# usbB_isp_no_lm2940.net
KiCad netlist of a schematic drawn in EAGLE
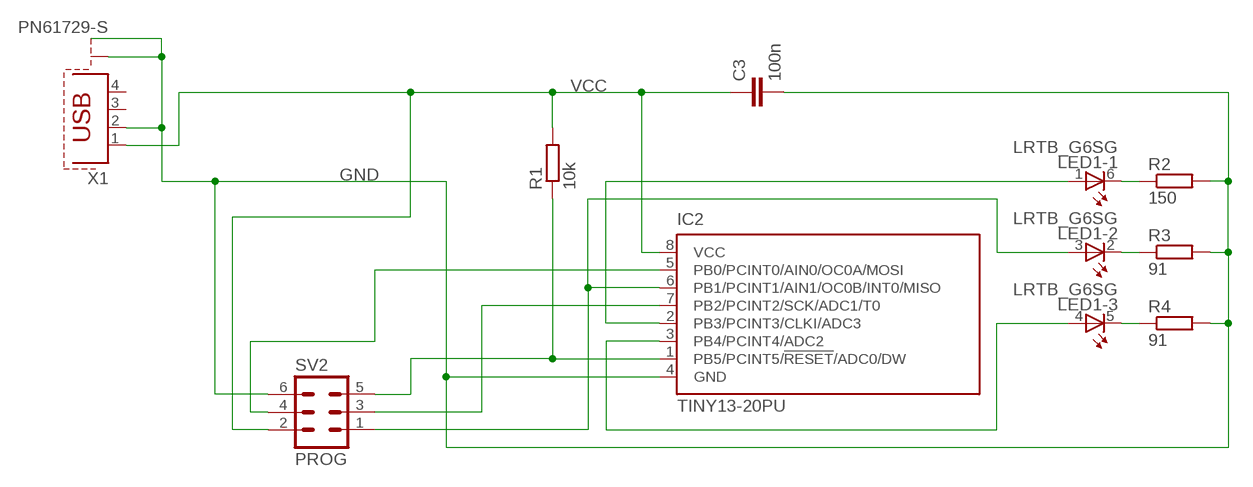
[diagram p0: schematic, sheet 1]

(export (version "E")
  (design (tool "Eeschema 10.0.6"))
  (components
    (comp (ref "C3")
      (value "100n")
      (footprint "eagle-import:C025-025X050")
      (libsource (lib "eagle-import") (part "C-EU025-025X050"))
    )
    (comp (ref "IC2")
      (value "TINY13-20PU")
      (footprint "eagle-import:DIL08")
      (fields (field (name "MPN") "ATTINY13-20PU"))
      (libsource (lib "eagle-import") (part "TINY13PU-20"))
    )
    (comp (ref "LED1")
      (value "LRTB_G6SG")
      (footprint "eagle-import:LRTB_G6SG")
      (libsource (lib "eagle-import") (part "LRTB_G6SG"))
    )
    (comp (ref "R1")
      (value "10k")
      (footprint "eagle-import:0207_10")
      (libsource (lib "eagle-import") (part "R-EU_0207/10"))
    )
    (comp (ref "R2")
      (value "150")
      (footprint "eagle-import:0207_10")
      (libsource (lib "eagle-import") (part "R-EU_0207/10"))
    )
    (comp (ref "R3")
      (value "91")
      (footprint "eagle-import:0207_10")
      (libsource (lib "eagle-import") (part "R-EU_0207/10"))
    )
    (comp (ref "R4")
      (value "91")
      (footprint "eagle-import:0207_10")
      (libsource (lib "eagle-import") (part "R-EU_0207/10"))
    )
    (comp (ref "SV2")
      (value "PROG")
      (footprint "eagle-import:ML6")
      (libsource (lib "eagle-import") (part "ML6"))
    )
    (comp (ref "X1")
      (value "PN61729-S")
      (footprint "eagle-import:PN61729-S")
      (libsource (lib "eagle-import") (part "PN61729-S"))
    )
  )
  (nets
    (net (code "1") (name "/GND") (class "Default")
      (node (ref "C3") (pin "2") (pinfunction "2_2") (pintype "passive"))
      (node (ref "IC2") (pin "4") (pinfunction "GND_4") (pintype "power_in"))
      (node (ref "R2") (pin "2") (pinfunction "2_2") (pintype "passive"))
      (node (ref "R3") (pin "2") (pinfunction "2_2") (pintype "passive"))
      (node (ref "R4") (pin "2") (pinfunction "2_2") (pintype "passive"))
      (node (ref "SV2") (pin "6") (pinfunction "6_6") (pintype "passive"))
      (node (ref "X1") (pin "2") (pinfunction "2_2") (pintype "passive"))
      (node (ref "X1") (pin "S1") (pinfunction "S1_S1") (pintype "passive"))
    )
    (net (code "2") (name "/VCC") (class "Default")
      (node (ref "C3") (pin "1") (pinfunction "1_1") (pintype "passive"))
      (node (ref "IC2") (pin "8") (pinfunction "VCC_8") (pintype "power_in"))
      (node (ref "R1") (pin "2") (pinfunction "2_2") (pintype "passive"))
      (node (ref "SV2") (pin "2") (pinfunction "2_2") (pintype "passive"))
      (node (ref "X1") (pin "1") (pinfunction "1_1") (pintype "passive"))
    )
    (net (code "3") (name "Net-(IC2-PB0{slash}PCINT0{slash}AIN0{slash}OC0A{slash}MOSI)") (class "Default")
      (node (ref "IC2") (pin "5") (pinfunction "PB0/PCINT0/AIN0/OC0A/MOSI_5") (pintype "bidirectional"))
      (node (ref "SV2") (pin "4") (pinfunction "4_4") (pintype "passive"))
    )
    (net (code "4") (name "Net-(IC2-PB1{slash}PCINT1{slash}AIN1{slash}OC0B{slash}INT0{slash}MISO)") (class "Default")
      (node (ref "IC2") (pin "6") (pinfunction "PB1/PCINT1/AIN1/OC0B/INT0/MISO_6") (pintype "bidirectional"))
      (node (ref "LED1") (pin "3") (pinfunction "A_3") (pintype "passive"))
      (node (ref "SV2") (pin "1") (pinfunction "1_1") (pintype "passive"))
    )
    (net (code "5") (name "Net-(IC2-PB2{slash}PCINT2{slash}SCK{slash}ADC1{slash}T0)") (class "Default")
      (node (ref "IC2") (pin "7") (pinfunction "PB2/PCINT2/SCK/ADC1/T0_7") (pintype "bidirectional"))
      (node (ref "SV2") (pin "3") (pinfunction "3_3") (pintype "passive"))
    )
    (net (code "6") (name "Net-(IC2-PB3{slash}PCINT3{slash}CLKI{slash}ADC3)") (class "Default")
      (node (ref "IC2") (pin "2") (pinfunction "PB3/PCINT3/CLKI/ADC3_2") (pintype "bidirectional"))
      (node (ref "LED1") (pin "1") (pinfunction "A_1") (pintype "passive"))
    )
    (net (code "7") (name "Net-(IC2-PB4{slash}PCINT4{slash}ADC2)") (class "Default")
      (node (ref "IC2") (pin "3") (pinfunction "PB4/PCINT4/ADC2_3") (pintype "bidirectional"))
      (node (ref "LED1") (pin "4") (pinfunction "A_4") (pintype "passive"))
    )
    (net (code "8") (name "Net-(IC2-PB5{slash}PCINT5{slash}~{RESET}{slash}ADC0{slash}DW)") (class "Default")
      (node (ref "IC2") (pin "1") (pinfunction "PB5/PCINT5/~{RESET}/ADC0/DW_1") (pintype "bidirectional"))
      (node (ref "R1") (pin "1") (pinfunction "1_1") (pintype "passive"))
      (node (ref "SV2") (pin "5") (pinfunction "5_5") (pintype "passive"))
    )
    (net (code "9") (name "Net-(LED1A-C)") (class "Default")
      (node (ref "LED1") (pin "6") (pinfunction "C_6") (pintype "passive"))
      (node (ref "R2") (pin "1") (pinfunction "1_1") (pintype "passive"))
    )
    (net (code "10") (name "Net-(LED1B-C)") (class "Default")
      (node (ref "LED1") (pin "2") (pinfunction "C_2") (pintype "passive"))
      (node (ref "R3") (pin "1") (pinfunction "1_1") (pintype "passive"))
    )
    (net (code "11") (name "Net-(LED1C-C)") (class "Default")
      (node (ref "LED1") (pin "5") (pinfunction "C_5") (pintype "passive"))
      (node (ref "R4") (pin "1") (pinfunction "1_1") (pintype "passive"))
    )
    (net (code "12") (name "unconnected-(X1-Pad3)") (class "Default")
      (node (ref "X1") (pin "3") (pinfunction "3_3") (pintype "passive"))
    )
    (net (code "13") (name "unconnected-(X1-Pad4)") (class "Default")
      (node (ref "X1") (pin "4") (pinfunction "4_4") (pintype "passive"))
    )
    (net (code "14") (name "unconnected-(X1-PadS2)") (class "Default")
      (node (ref "X1") (pin "S2") (pinfunction "S2_S2") (pintype "passive"))
    )
  )
)
